# Relay.net
KiCad netlist of a schematic drawn in Altium Designer
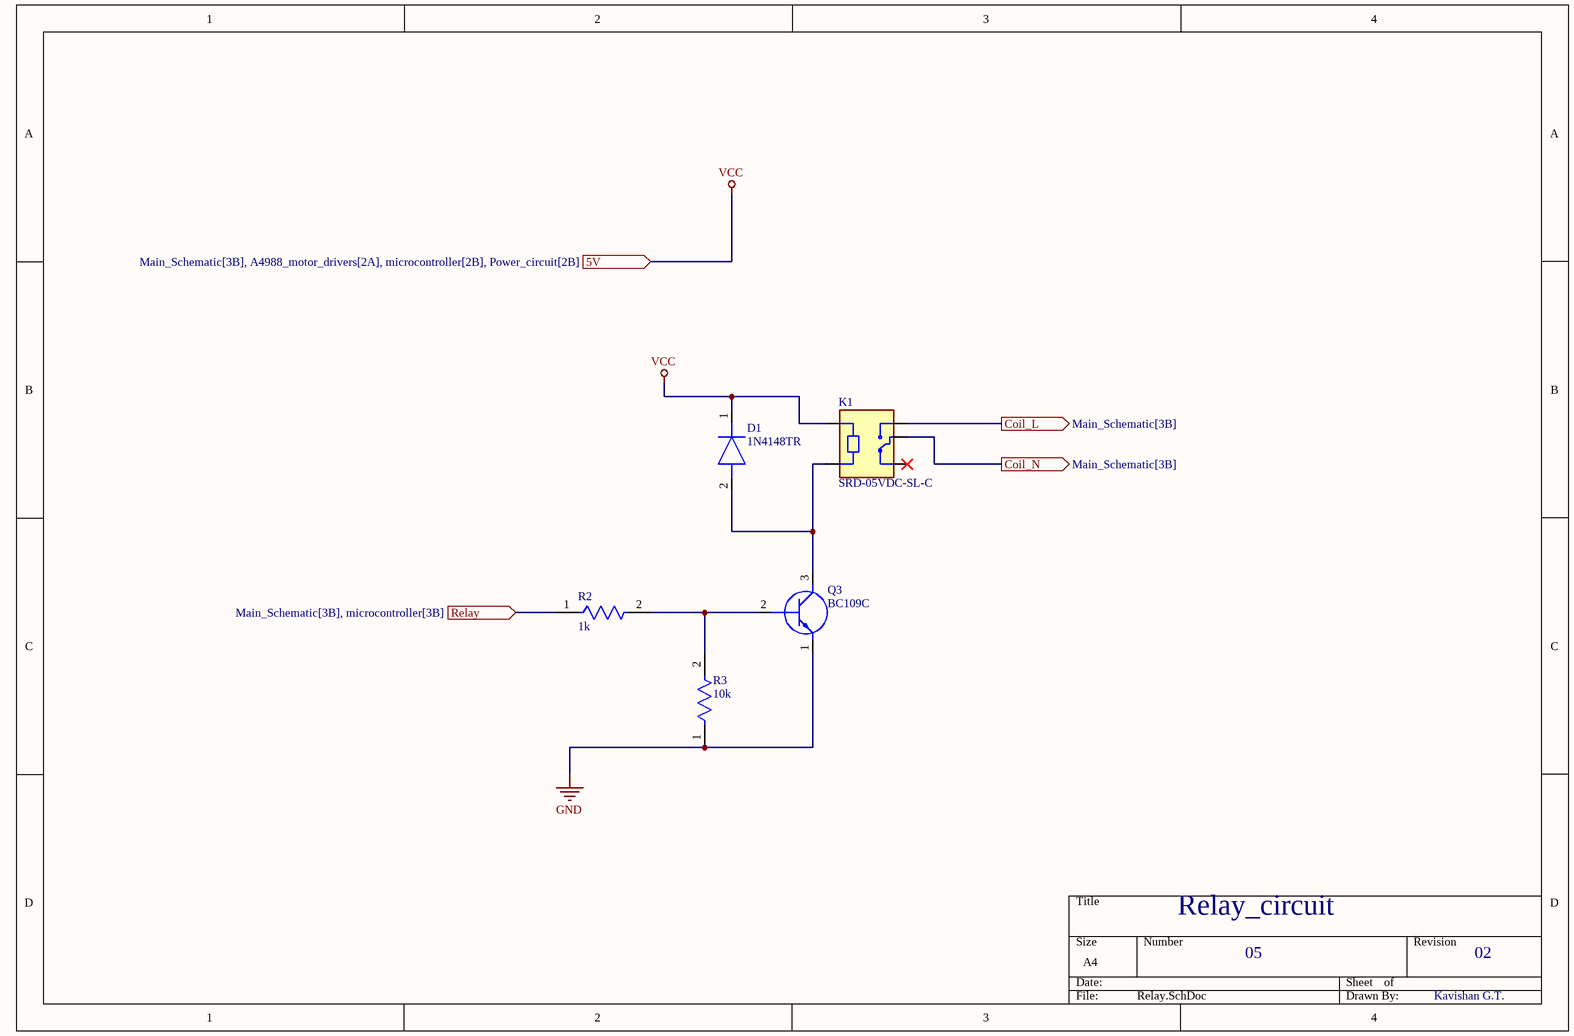
[diagram p0: Relay.SchDoc]

(export (version "E")
  (design (tool "Eeschema 10.0.6"))
  (components
    (comp (ref "D1")
      (value "1N4148TR")
      (footprint "SamacSys:DIOAD990W55L340D162")
      (description "Diode")
      (fields (field (name "MOUSER PART NUMBER") "78-1N4148"))
      (libsource (lib "*") (part "1N4148TR"))
    )
    (comp (ref "K1")
      (value "SRD-05VDC-SL-C")
      (footprint "RELAY_SRD-05VDC-SL-C")
      (fields (field (name "MF") "Songle Relay"))
      (libsource (lib "SRD-05VDC-SL-C") (part "SRD-05VDC-SL-C"))
    )
    (comp (ref "Q3")
      (value "BC109C")
      (footprint "SamacSys:CENTRAL_TO18")
      (description "Transistor BJT NPN")
      (fields (field (name "MOUSER PART NUMBER") "610-BC109C"))
      (libsource (lib "*") (part "BC109C"))
    )
    (comp (ref "R2")
      (value "1k")
      (footprint "FP-MFR-25-MFG")
      (description "RES 1.18K OHM 1/4W 1% AXIAL")
      (fields (field (name "MANUFACTURER") "Yageo") (field (name "TOLERANCE") "1%"))
      (libsource (lib "Altium Content Vault") (part "1029c3af85768c4190bb7ad29bc67b5"))
    )
    (comp (ref "R3")
      (value "10k")
      (footprint "FP-MFR-25-MFG")
      (description "RES 1.18K OHM 1/4W 1% AXIAL")
      (fields (field (name "MANUFACTURER") "Yageo") (field (name "TOLERANCE") "1%"))
      (libsource (lib "Altium Content Vault") (part "1029c3af85768c4190bb7ad29bc67b5"))
    )
  )
  (nets
    (net (code "1") (name "/Coil_L") (class "Default")
      (node (ref "K1") (pin "NO") (pinfunction "NO_NO") (pintype "passive"))
    )
    (net (code "2") (name "/Coil_N") (class "Default")
      (node (ref "K1") (pin "COM") (pinfunction "COM_COM") (pintype "passive"))
    )
    (net (code "3") (name "/Relay") (class "Default")
      (node (ref "R2") (pin "1") (pinfunction "1_1") (pintype "passive"))
    )
    (net (code "4") (name "GND") (class "Default")
      (node (ref "Q3") (pin "1") (pinfunction "E_1") (pintype "passive"))
      (node (ref "R3") (pin "1") (pinfunction "1_1") (pintype "passive"))
    )
    (net (code "5") (name "Net-(D1-A)") (class "Default")
      (node (ref "D1") (pin "2") (pinfunction "A_2") (pintype "passive"))
      (node (ref "K1") (pin "A2") (pinfunction "A2_A2") (pintype "passive"))
      (node (ref "Q3") (pin "3") (pinfunction "C_3") (pintype "passive"))
    )
    (net (code "6") (name "Net-(Q3-B)") (class "Default")
      (node (ref "Q3") (pin "2") (pinfunction "B_2") (pintype "passive"))
      (node (ref "R2") (pin "2") (pinfunction "2_2") (pintype "passive"))
      (node (ref "R3") (pin "2") (pinfunction "2_2") (pintype "passive"))
    )
    (net (code "7") (name "VCC") (class "Default")
      (node (ref "D1") (pin "1") (pinfunction "K_1") (pintype "passive"))
      (node (ref "K1") (pin "A1") (pinfunction "A1_A1") (pintype "passive"))
    )
    (net (code "8") (name "unconnected-(K1-PadNC)") (class "Default")
      (node (ref "K1") (pin "NC") (pinfunction "NC_NC") (pintype "passive+no_connect"))
    )
  )
)
